# CON_PWR_RJ45.net
KiCad netlist of a schematic drawn in Altium Designer
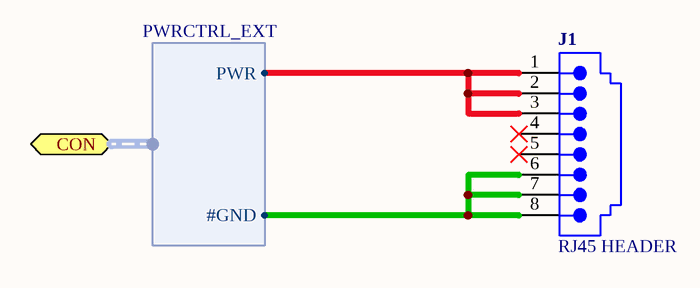
[diagram p0: CON_PWR_RJ45.SchDoc]

(export (version "E")
  (design (tool "Eeschema 10.0.6"))
  (components
    (comp (ref "J1")
      (value "RJ45 HEADER")
      (footprint "15-43-6233")
      (description "Connector, RJ45 Socket, Right-Angle, 8 Way (Ethernet), PCM8P8C")
      (libsource (lib "AltiumDesignLibrary") (part "CON-RJ45-8-RA"))
    )
  )
  (nets
    (net (code "3") (name "Net-(J1-Pad1)") (class "Default")
      (node (ref "J1") (pin "1") (pinfunction "1_1") (pintype "passive"))
      (node (ref "J1") (pin "2") (pinfunction "2_2") (pintype "passive"))
      (node (ref "J1") (pin "3") (pinfunction "3_3") (pintype "passive"))
    )
    (net (code "4") (name "Net-(J1-Pad6)") (class "Default")
      (node (ref "J1") (pin "6") (pinfunction "6_6") (pintype "passive"))
      (node (ref "J1") (pin "7") (pinfunction "7_7") (pintype "passive"))
      (node (ref "J1") (pin "8") (pinfunction "8_8") (pintype "passive"))
    )
    (net (code "5") (name "unconnected-(J1-Pad4)") (class "Default")
      (node (ref "J1") (pin "4") (pinfunction "4_4") (pintype "passive+no_connect"))
    )
    (net (code "6") (name "unconnected-(J1-Pad5)") (class "Default")
      (node (ref "J1") (pin "5") (pinfunction "5_5") (pintype "passive+no_connect"))
    )
  )
)
